# DWM1000.net
KiCad netlist of a schematic drawn in EAGLE
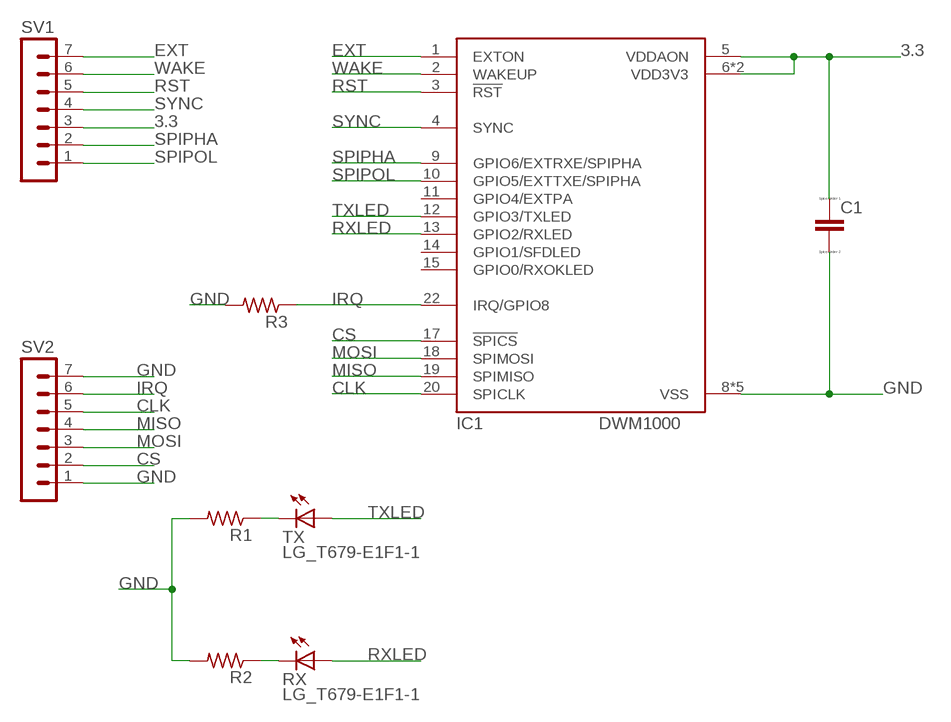
[diagram p0: schematic, sheet 1]

(export (version "E")
  (design (tool "Eeschema 10.0.6"))
  (components
    (comp (ref "C1")
      (value "CC0504")
      (footprint "eagle-import:C0504")
      (libsource (lib "eagle-import") (part "CC0504"))
    )
    (comp (ref "IC1")
      (value "DWM1000")
      (footprint "eagle-import:DWM1000")
      (libsource (lib "eagle-import") (part "DWM1000"))
    )
    (comp (ref "R1")
      (value "R-US_M0805")
      (footprint "eagle-import:M0805")
      (libsource (lib "eagle-import") (part "R-US_M0805"))
    )
    (comp (ref "R2")
      (value "R-US_M0805")
      (footprint "eagle-import:M0805")
      (libsource (lib "eagle-import") (part "R-US_M0805"))
    )
    (comp (ref "R3")
      (value "R-US_M0805")
      (footprint "eagle-import:M0805")
      (libsource (lib "eagle-import") (part "R-US_M0805"))
    )
    (comp (ref "RX")
      (value "LG_T679-E1F1-1")
      (footprint "eagle-import:PLCC2")
      (libsource (lib "eagle-import") (part "_T679-?-1E1F1LG"))
    )
    (comp (ref "SV1")
      (value "MA07-1")
      (footprint "eagle-import:MA07-1")
      (libsource (lib "eagle-import") (part "MA07-1"))
    )
    (comp (ref "SV2")
      (value "MA07-1")
      (footprint "eagle-import:MA07-1")
      (libsource (lib "eagle-import") (part "MA07-1"))
    )
    (comp (ref "TX")
      (value "LG_T679-E1F1-1")
      (footprint "eagle-import:PLCC2")
      (libsource (lib "eagle-import") (part "_T679-?-1E1F1LG"))
    )
  )
  (nets
    (net (code "1") (name "/3.3") (class "Default")
      (node (ref "C1") (pin "1") (pinfunction "1_1") (pintype "passive"))
      (node (ref "IC1") (pin "5") (pinfunction "VDDAON_5") (pintype "bidirectional"))
      (node (ref "IC1") (pin "6") (pinfunction "VDD3V3_6") (pintype "bidirectional"))
      (node (ref "IC1") (pin "7") (pinfunction "VDD3V3_7") (pintype "bidirectional"))
      (node (ref "SV1") (pin "3") (pinfunction "3_3") (pintype "passive"))
    )
    (net (code "2") (name "/CLK") (class "Default")
      (node (ref "IC1") (pin "20") (pinfunction "SPICLK_20") (pintype "bidirectional"))
      (node (ref "SV2") (pin "5") (pinfunction "5_5") (pintype "passive"))
    )
    (net (code "3") (name "/CS") (class "Default")
      (node (ref "IC1") (pin "17") (pinfunction "~{SPICS}_17") (pintype "bidirectional"))
      (node (ref "SV2") (pin "2") (pinfunction "2_2") (pintype "passive"))
    )
    (net (code "4") (name "/EXT") (class "Default")
      (node (ref "IC1") (pin "1") (pinfunction "EXTON_1") (pintype "bidirectional"))
      (node (ref "SV1") (pin "7") (pinfunction "7_7") (pintype "passive"))
    )
    (net (code "5") (name "/GND") (class "Default")
      (node (ref "C1") (pin "2") (pinfunction "2_2") (pintype "passive"))
      (node (ref "IC1") (pin "16") (pinfunction "VSS_16") (pintype "bidirectional"))
      (node (ref "IC1") (pin "21") (pinfunction "VSS_21") (pintype "bidirectional"))
      (node (ref "IC1") (pin "23") (pinfunction "VSS_23") (pintype "bidirectional"))
      (node (ref "IC1") (pin "24") (pinfunction "VSS_24") (pintype "bidirectional"))
      (node (ref "IC1") (pin "8") (pinfunction "VSS_8") (pintype "bidirectional"))
      (node (ref "R1") (pin "2") (pinfunction "2_2") (pintype "passive"))
      (node (ref "R2") (pin "2") (pinfunction "2_2") (pintype "passive"))
      (node (ref "R3") (pin "2") (pinfunction "2_2") (pintype "passive"))
      (node (ref "SV2") (pin "1") (pinfunction "1_1") (pintype "passive"))
      (node (ref "SV2") (pin "7") (pinfunction "7_7") (pintype "passive"))
    )
    (net (code "6") (name "/IRQ") (class "Default")
      (node (ref "IC1") (pin "22") (pinfunction "IRQ/GPIO8_22") (pintype "bidirectional"))
      (node (ref "R3") (pin "1") (pinfunction "1_1") (pintype "passive"))
      (node (ref "SV2") (pin "6") (pinfunction "6_6") (pintype "passive"))
    )
    (net (code "7") (name "/MISO") (class "Default")
      (node (ref "IC1") (pin "19") (pinfunction "SPIMISO_19") (pintype "bidirectional"))
      (node (ref "SV2") (pin "4") (pinfunction "4_4") (pintype "passive"))
    )
    (net (code "8") (name "/MOSI") (class "Default")
      (node (ref "IC1") (pin "18") (pinfunction "SPIMOSI_18") (pintype "bidirectional"))
      (node (ref "SV2") (pin "3") (pinfunction "3_3") (pintype "passive"))
    )
    (net (code "9") (name "/RST") (class "Default")
      (node (ref "IC1") (pin "3") (pinfunction "~{RST}_3") (pintype "bidirectional"))
      (node (ref "SV1") (pin "5") (pinfunction "5_5") (pintype "passive"))
    )
    (net (code "10") (name "/RXLED") (class "Default")
      (node (ref "IC1") (pin "13") (pinfunction "GPIO2/RXLED_13") (pintype "bidirectional"))
      (node (ref "RX") (pin "A") (pinfunction "A_A") (pintype "passive"))
    )
    (net (code "11") (name "/SPIPHA") (class "Default")
      (node (ref "IC1") (pin "9") (pinfunction "GPIO6/EXTRXE/SPIPHA_9") (pintype "bidirectional"))
      (node (ref "SV1") (pin "2") (pinfunction "2_2") (pintype "passive"))
    )
    (net (code "12") (name "/SPIPOL") (class "Default")
      (node (ref "IC1") (pin "10") (pinfunction "GPIO5/EXTTXE/SPIPHA_10") (pintype "bidirectional"))
      (node (ref "SV1") (pin "1") (pinfunction "1_1") (pintype "passive"))
    )
    (net (code "13") (name "/SYNC") (class "Default")
      (node (ref "IC1") (pin "4") (pinfunction "SYNC_4") (pintype "bidirectional"))
      (node (ref "SV1") (pin "4") (pinfunction "4_4") (pintype "passive"))
    )
    (net (code "14") (name "/TXLED") (class "Default")
      (node (ref "IC1") (pin "12") (pinfunction "GPIO3/TXLED_12") (pintype "bidirectional"))
      (node (ref "TX") (pin "A") (pinfunction "A_A") (pintype "passive"))
    )
    (net (code "15") (name "/WAKE") (class "Default")
      (node (ref "IC1") (pin "2") (pinfunction "WAKEUP_2") (pintype "bidirectional"))
      (node (ref "SV1") (pin "6") (pinfunction "6_6") (pintype "passive"))
    )
    (net (code "16") (name "Net-(R1-Pad1)") (class "Default")
      (node (ref "R1") (pin "1") (pinfunction "1_1") (pintype "passive"))
      (node (ref "TX") (pin "C") (pinfunction "C_C") (pintype "passive"))
    )
    (net (code "17") (name "Net-(R2-Pad1)") (class "Default")
      (node (ref "R2") (pin "1") (pinfunction "1_1") (pintype "passive"))
      (node (ref "RX") (pin "C") (pinfunction "C_C") (pintype "passive"))
    )
    (net (code "18") (name "unconnected-(IC1-GPIO0{slash}RXOKLED-Pad15)") (class "Default")
      (node (ref "IC1") (pin "15") (pinfunction "GPIO0/RXOKLED_15") (pintype "bidirectional"))
    )
    (net (code "19") (name "unconnected-(IC1-GPIO1{slash}SFDLED-Pad14)") (class "Default")
      (node (ref "IC1") (pin "14") (pinfunction "GPIO1/SFDLED_14") (pintype "bidirectional"))
    )
    (net (code "20") (name "unconnected-(IC1-GPIO4{slash}EXTPA-Pad11)") (class "Default")
      (node (ref "IC1") (pin "11") (pinfunction "GPIO4/EXTPA_11") (pintype "bidirectional"))
    )
  )
)
